# STM32103C8T6.net
KiCad netlist of a schematic drawn in Altium Designer
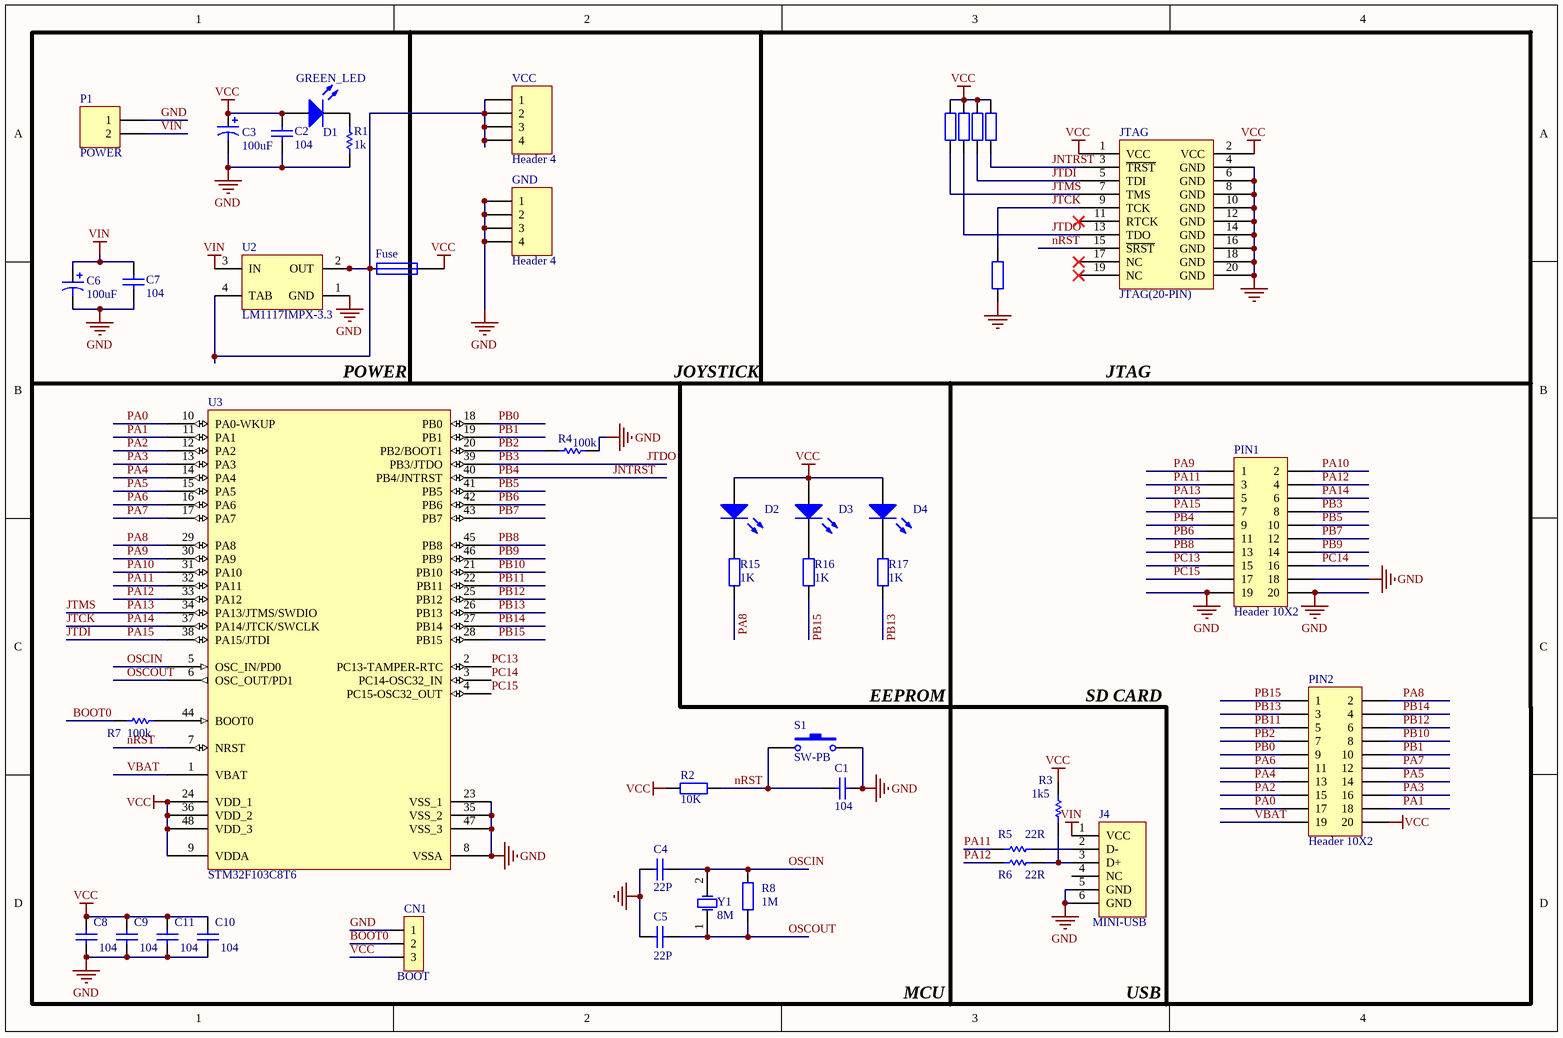
[diagram p0: STM32103C8T6.SchDoc]

(export (version "E")
  (design (tool "Eeschema 10.0.6"))
  (components
    (comp (ref "C1")
      (value "104")
      (footprint "0805")
      (description "Capacitor (Semiconductor SIM Model)")
      (fields (field (name "Comment") "Cap Semi") (field (name "PUBLISHER") "Altium Limited"))
      (libsource (lib "Miscellaneous Devices") (part "Cap Semi"))
    )
    (comp (ref "C2")
      (value "104")
      (footprint "0805")
      (description "Capacitor (Semiconductor SIM Model)")
      (fields (field (name "Comment") "Cap Semi") (field (name "PUBLISHER") "Altium Limited"))
      (libsource (lib "Miscellaneous Devices") (part "Cap Semi"))
    )
    (comp (ref "C3")
      (value "100uF")
      (footprint "1206")
      (description "Polarized Capacitor (Radial)")
      (fields (field (name "Comment") "Cap Pol1") (field (name "PUBLISHER") "Altium Limited"))
      (libsource (lib "Miscellaneous Devices") (part "Cap Pol1"))
    )
    (comp (ref "C4")
      (value "22P")
      (footprint "0805")
      (description "Capacitor")
      (fields (field (name "PUBLISHER") "Altium Limited"))
      (libsource (lib "Miscellaneous Devices") (part "Cap"))
    )
    (comp (ref "C5")
      (value "22P")
      (footprint "0805")
      (description "Capacitor")
      (fields (field (name "PUBLISHER") "Altium Limited"))
      (libsource (lib "Miscellaneous Devices") (part "Cap"))
    )
    (comp (ref "C6")
      (value "100uF")
      (footprint "1206")
      (description "Polarized Capacitor (Radial)")
      (fields (field (name "Comment") "Cap Pol1") (field (name "PUBLISHER") "Altium Limited"))
      (libsource (lib "Miscellaneous Devices") (part "Cap Pol1"))
    )
    (comp (ref "C7")
      (value "104")
      (footprint "0805")
      (description "Capacitor (Semiconductor SIM Model)")
      (fields (field (name "Comment") "Cap Semi") (field (name "PUBLISHER") "Altium Limited"))
      (libsource (lib "Miscellaneous Devices") (part "Cap Semi"))
    )
    (comp (ref "C8")
      (value "104")
      (footprint "0603")
      (description "Capacitor (Semiconductor SIM Model)")
      (fields (field (name "Comment") "Cap Semi") (field (name "PUBLISHER") "Altium Limited"))
      (libsource (lib "Miscellaneous Devices") (part "Cap Semi"))
    )
    (comp (ref "C9")
      (value "104")
      (footprint "0603")
      (description "Capacitor (Semiconductor SIM Model)")
      (fields (field (name "Comment") "Cap Semi") (field (name "PUBLISHER") "Altium Limited"))
      (libsource (lib "Miscellaneous Devices") (part "Cap Semi"))
    )
    (comp (ref "C10")
      (value "104")
      (footprint "0603")
      (description "Capacitor (Semiconductor SIM Model)")
      (fields (field (name "Comment") "Cap Semi") (field (name "PUBLISHER") "Altium Limited"))
      (libsource (lib "Miscellaneous Devices") (part "Cap Semi"))
    )
    (comp (ref "C11")
      (value "104")
      (footprint "0603")
      (description "Capacitor (Semiconductor SIM Model)")
      (fields (field (name "Comment") "Cap Semi") (field (name "PUBLISHER") "Altium Limited"))
      (libsource (lib "Miscellaneous Devices") (part "Cap Semi"))
    )
    (comp (ref "CN1") (value "BOOT") (footprint "KEY_22D00") (libsource (lib "Universal") (part "CON3")))
    (comp (ref "D1")
      (value "GREEN_LED")
      (footprint "LED_0805")
      (description "Typical BLUE SiC LED")
      (fields (field (name "PUBLISHER") "Altium Limited"))
      (libsource (lib "Miscellaneous Devices") (part "LED3"))
    )
    (comp (ref "D2")
      (value "LED0")
      (footprint "0805")
      (description "Typical INFRARED GaAs LED")
      (fields (field (name "PUBLISHER") "Altium Limited"))
      (libsource (lib "Miscellaneous Devices") (part "LED0"))
    )
    (comp (ref "D3")
      (value "LED0")
      (footprint "0805")
      (description "Typical INFRARED GaAs LED")
      (fields (field (name "PUBLISHER") "Altium Limited"))
      (libsource (lib "Miscellaneous Devices") (part "LED0"))
    )
    (comp (ref "D4")
      (value "LED0")
      (footprint "0805")
      (description "Typical INFRARED GaAs LED")
      (fields (field (name "PUBLISHER") "Altium Limited"))
      (libsource (lib "Miscellaneous Devices") (part "LED0"))
    )
    (comp (ref "Fuse")
      (value "Fuse 1")
      (footprint "0805")
      (description "Fuse")
      (fields (field (name "PUBLISHER") "Altium Limited"))
      (libsource (lib "Miscellaneous Devices") (part "Fuse 1"))
    )
    (comp (ref "GND")
      (value "Header 4")
      (footprint "HDR1X4")
      (description "Header, 4-Pin")
      (fields (field (name "PUBLISHER") "Altium Limited"))
      (libsource (lib "Miscellaneous Connectors") (part "Header 4"))
    )
    (comp (ref "J4")
      (value "MINI-USB")
      (footprint "MINI_USB")
      (libsource (lib "Universal") (part "USB-MINI"))
    )
    (comp (ref "JTAG")
      (value "JTAG(20-PIN)")
      (footprint "JP20_DOMNLOAD")
      (libsource (lib "LM3S_JTAG") (part "JTAG(20-PIN)"))
    )
    (comp (ref "P1")
      (value "POWER")
      (footprint "XH2.54-2")
      (description "Header, 2-Pin")
      (fields (field (name "PUBLISHER") "Altium Limited"))
      (libsource (lib "Miscellaneous Connectors") (part "Header 2"))
    )
    (comp (ref "PIN1")
      (value "Header 10X2")
      (footprint "HDR2X10")
      (description "Header, 10-Pin, Dual row")
      (fields (field (name "PUBLISHER") "Altium Limited"))
      (libsource (lib "Miscellaneous Connectors") (part "Header 10X2"))
    )
    (comp (ref "PIN2")
      (value "Header 10X2")
      (footprint "HDR2X10")
      (description "Header, 10-Pin, Dual row")
      (fields (field (name "PUBLISHER") "Altium Limited"))
      (libsource (lib "Miscellaneous Connectors") (part "Header 10X2"))
    )
    (comp (ref "R1")
      (value "1k")
      (footprint "0805")
      (description "Semiconductor Resistor")
      (fields (field (name "Comment") "Res Semi") (field (name "PUBLISHER") "Altium Limited"))
      (libsource (lib "Miscellaneous Devices") (part "Res Semi"))
    )
    (comp (ref "R2")
      (value "10K")
      (footprint "0805")
      (description "Resistor")
      (fields (field (name "Comment") "Res2") (field (name "PUBLISHER") "Altium Limited"))
      (libsource (lib "") (part "Res2_2"))
    )
    (comp (ref "R3")
      (value "1k5")
      (footprint "0805")
      (description "Semiconductor Resistor")
      (fields (field (name "Comment") "Res Semi") (field (name "PUBLISHER") "Altium Limited"))
      (libsource (lib "Miscellaneous Devices") (part "Res Semi"))
    )
    (comp (ref "R4")
      (value "100k")
      (footprint "0805")
      (description "Semiconductor Resistor")
      (fields (field (name "Comment") "Res Semi") (field (name "PUBLISHER") "Altium Limited"))
      (libsource (lib "Miscellaneous Devices") (part "Res Semi"))
    )
    (comp (ref "R5")
      (value "22R")
      (footprint "0805")
      (description "Semiconductor Resistor")
      (fields (field (name "Comment") "Res Semi") (field (name "PUBLISHER") "Altium Limited"))
      (libsource (lib "Miscellaneous Devices") (part "Res Semi"))
    )
    (comp (ref "R6")
      (value "22R")
      (footprint "0805")
      (description "Semiconductor Resistor")
      (fields (field (name "Comment") "Res Semi") (field (name "PUBLISHER") "Altium Limited"))
      (libsource (lib "Miscellaneous Devices") (part "Res Semi"))
    )
    (comp (ref "R7")
      (value "100k")
      (footprint "0805")
      (description "Semiconductor Resistor")
      (fields (field (name "Comment") "Res Semi") (field (name "PUBLISHER") "Altium Limited"))
      (libsource (lib "Miscellaneous Devices") (part "Res Semi"))
    )
    (comp (ref "R8")
      (value "1M")
      (footprint "0805")
      (description "Resistor")
      (fields (field (name "PUBLISHER") "Altium Limited"))
      (libsource (lib "") (part "Res2_1"))
    )
    (comp (ref "R10")
      (value "10K")
      (footprint "0805")
      (description "Resistor")
      (fields (field (name "PUBLISHER") "Altium Limited"))
      (libsource (lib "Miscellaneous Devices") (part "Res2"))
    )
    (comp (ref "R11")
      (value "10K")
      (footprint "0805")
      (description "Resistor")
      (fields (field (name "PUBLISHER") "Altium Limited"))
      (libsource (lib "Miscellaneous Devices") (part "Res2"))
    )
    (comp (ref "R12")
      (value "10K")
      (footprint "0805")
      (description "Resistor")
      (fields (field (name "PUBLISHER") "Altium Limited"))
      (libsource (lib "Miscellaneous Devices") (part "Res2"))
    )
    (comp (ref "R13")
      (value "10K")
      (footprint "0805")
      (description "Resistor")
      (fields (field (name "PUBLISHER") "Altium Limited"))
      (libsource (lib "Miscellaneous Devices") (part "Res2"))
    )
    (comp (ref "R14")
      (value "10K")
      (footprint "0805")
      (description "Resistor")
      (fields (field (name "PUBLISHER") "Altium Limited"))
      (libsource (lib "Miscellaneous Devices") (part "Res2"))
    )
    (comp (ref "R15")
      (value "1K")
      (footprint "0805")
      (description "Resistor")
      (fields (field (name "PUBLISHER") "Altium Limited"))
      (libsource (lib "") (part "Res2_1"))
    )
    (comp (ref "R16")
      (value "1K")
      (footprint "0805")
      (description "Resistor")
      (fields (field (name "PUBLISHER") "Altium Limited"))
      (libsource (lib "") (part "Res2_1"))
    )
    (comp (ref "R17")
      (value "1K")
      (footprint "0805")
      (description "Resistor")
      (fields (field (name "PUBLISHER") "Altium Limited"))
      (libsource (lib "") (part "Res2_1"))
    )
    (comp (ref "S1")
      (value "SW-PB")
      (footprint "棕色小按键开关")
      (description "Switch")
      (fields (field (name "PUBLISHER") "Altium Limited"))
      (libsource (lib "Miscellaneous Devices") (part "SW-PB"))
    )
    (comp (ref "U2")
      (value "LM1117IMPX-3.3")
      (footprint "MP04A_N")
      (description "800mA Low-Dropout Linear Regulator, 4-pin SOT-223")
      (fields
        (field (name "MANUFACTURER") "National Semiconductor")
        (field (name "PUBLISHER") "Altium Limited")
      )
      (libsource (lib "NSC LDO") (part "LM1117IMPX-3.3"))
    )
    (comp (ref "U3")
      (value "STM32F103C8T6")
      (footprint "LQFP48_L")
      (description "STM32 ARM-based 32-bit MCU with 64 Kbytes Flash, 48-pin LQFP, Industrial Temperature")
      (libsource (lib "ST Microcontroller 32-Bit STM32 SCH") (part "STM32F103C8T6"))
    )
    (comp (ref "VCC")
      (value "Header 4")
      (footprint "HDR1X4")
      (description "Header, 4-Pin")
      (fields (field (name "PUBLISHER") "Altium Limited"))
      (libsource (lib "Miscellaneous Connectors") (part "Header 4"))
    )
    (comp (ref "Y1")
      (value "8M")
      (footprint "XTAL")
      (description "Crystal Oscillator")
      (fields (field (name "PUBLISHER") "Altium Limited"))
      (libsource (lib "Miscellaneous Devices") (part "XTAL"))
    )
  )
  (nets
    (net (code "1") (name "/BOOT0") (class "Default")
      (node (ref "CN1") (pin "2") (pinfunction "2_2") (pintype "passive"))
      (node (ref "R7") (pin "1") (pinfunction "1_1") (pintype "passive"))
    )
    (net (code "2") (name "/JNTRST") (class "Default")
      (node (ref "JTAG") (pin "3") (pinfunction "~{TRST}_3") (pintype "passive"))
      (node (ref "PIN1") (pin "9") (pinfunction "9_9") (pintype "passive"))
      (node (ref "R14") (pin "1") (pinfunction "1_1") (pintype "passive"))
      (node (ref "U3") (pin "40") (pinfunction "PB4/JNTRST_40") (pintype "bidirectional"))
    )
    (net (code "3") (name "/JTCK") (class "Default")
      (node (ref "JTAG") (pin "9") (pinfunction "TCK_9") (pintype "passive"))
      (node (ref "PIN1") (pin "6") (pinfunction "6_6") (pintype "passive"))
      (node (ref "R10") (pin "2") (pinfunction "2_2") (pintype "passive"))
      (node (ref "U3") (pin "37") (pinfunction "PA14/JTCK/SWCLK_37") (pintype "bidirectional"))
    )
    (net (code "4") (name "/JTDI") (class "Default")
      (node (ref "JTAG") (pin "5") (pinfunction "TDI_5") (pintype "passive"))
      (node (ref "PIN1") (pin "7") (pinfunction "7_7") (pintype "passive"))
      (node (ref "R13") (pin "1") (pinfunction "1_1") (pintype "passive"))
      (node (ref "U3") (pin "38") (pinfunction "PA15/JTDI_38") (pintype "bidirectional"))
    )
    (net (code "5") (name "/JTDO") (class "Default")
      (node (ref "JTAG") (pin "13") (pinfunction "TDO_13") (pintype "passive"))
      (node (ref "PIN1") (pin "8") (pinfunction "8_8") (pintype "passive"))
      (node (ref "R12") (pin "1") (pinfunction "1_1") (pintype "passive"))
      (node (ref "U3") (pin "39") (pinfunction "PB3/JTDO_39") (pintype "bidirectional"))
    )
    (net (code "6") (name "/JTMS") (class "Default")
      (node (ref "JTAG") (pin "7") (pinfunction "TMS_7") (pintype "passive"))
      (node (ref "PIN1") (pin "5") (pinfunction "5_5") (pintype "passive"))
      (node (ref "R11") (pin "1") (pinfunction "1_1") (pintype "passive"))
      (node (ref "U3") (pin "34") (pinfunction "PA13/JTMS/SWDIO_34") (pintype "bidirectional"))
    )
    (net (code "7") (name "/OSCIN") (class "Default")
      (node (ref "C4") (pin "1") (pinfunction "1_1") (pintype "passive"))
      (node (ref "R8") (pin "2") (pinfunction "2_2") (pintype "passive"))
      (node (ref "U3") (pin "5") (pinfunction "OSC_IN/PD0_5") (pintype "input"))
      (node (ref "Y1") (pin "2") (pinfunction "OSC2_2") (pintype "passive"))
    )
    (net (code "8") (name "/OSCOUT") (class "Default")
      (node (ref "C5") (pin "1") (pinfunction "1_1") (pintype "passive"))
      (node (ref "R8") (pin "1") (pinfunction "1_1") (pintype "passive"))
      (node (ref "U3") (pin "6") (pinfunction "OSC_OUT/PD1_6") (pintype "output"))
      (node (ref "Y1") (pin "1") (pinfunction "OSC1_1") (pintype "passive"))
    )
    (net (code "9") (name "/PA0") (class "Default")
      (node (ref "PIN2") (pin "17") (pinfunction "17_17") (pintype "passive"))
      (node (ref "U3") (pin "10") (pinfunction "PA0-WKUP_10") (pintype "bidirectional"))
    )
    (net (code "10") (name "/PA1") (class "Default")
      (node (ref "PIN2") (pin "18") (pinfunction "18_18") (pintype "passive"))
      (node (ref "U3") (pin "11") (pinfunction "PA1_11") (pintype "bidirectional"))
    )
    (net (code "11") (name "/PA2") (class "Default")
      (node (ref "PIN2") (pin "15") (pinfunction "15_15") (pintype "passive"))
      (node (ref "U3") (pin "12") (pinfunction "PA2_12") (pintype "bidirectional"))
    )
    (net (code "12") (name "/PA3") (class "Default")
      (node (ref "PIN2") (pin "16") (pinfunction "16_16") (pintype "passive"))
      (node (ref "U3") (pin "13") (pinfunction "PA3_13") (pintype "bidirectional"))
    )
    (net (code "13") (name "/PA4") (class "Default")
      (node (ref "PIN2") (pin "13") (pinfunction "13_13") (pintype "passive"))
      (node (ref "U3") (pin "14") (pinfunction "PA4_14") (pintype "bidirectional"))
    )
    (net (code "14") (name "/PA5") (class "Default")
      (node (ref "PIN2") (pin "14") (pinfunction "14_14") (pintype "passive"))
      (node (ref "U3") (pin "15") (pinfunction "PA5_15") (pintype "bidirectional"))
    )
    (net (code "15") (name "/PA6") (class "Default")
      (node (ref "PIN2") (pin "11") (pinfunction "11_11") (pintype "passive"))
      (node (ref "U3") (pin "16") (pinfunction "PA6_16") (pintype "bidirectional"))
    )
    (net (code "16") (name "/PA7") (class "Default")
      (node (ref "PIN2") (pin "12") (pinfunction "12_12") (pintype "passive"))
      (node (ref "U3") (pin "17") (pinfunction "PA7_17") (pintype "bidirectional"))
    )
    (net (code "17") (name "/PA8") (class "Default")
      (node (ref "PIN2") (pin "2") (pinfunction "2_2") (pintype "passive"))
      (node (ref "R15") (pin "1") (pinfunction "1_1") (pintype "passive"))
      (node (ref "U3") (pin "29") (pinfunction "PA8_29") (pintype "bidirectional"))
    )
    (net (code "18") (name "/PA9") (class "Default")
      (node (ref "PIN1") (pin "1") (pinfunction "1_1") (pintype "passive"))
      (node (ref "U3") (pin "30") (pinfunction "PA9_30") (pintype "bidirectional"))
    )
    (net (code "19") (name "/PA10") (class "Default")
      (node (ref "PIN1") (pin "2") (pinfunction "2_2") (pintype "passive"))
      (node (ref "U3") (pin "31") (pinfunction "PA10_31") (pintype "bidirectional"))
    )
    (net (code "20") (name "/PA11") (class "Default")
      (node (ref "PIN1") (pin "3") (pinfunction "3_3") (pintype "passive"))
      (node (ref "R5") (pin "1") (pinfunction "1_1") (pintype "passive"))
      (node (ref "U3") (pin "32") (pinfunction "PA11_32") (pintype "bidirectional"))
    )
    (net (code "21") (name "/PA12") (class "Default")
      (node (ref "PIN1") (pin "4") (pinfunction "4_4") (pintype "passive"))
      (node (ref "R6") (pin "1") (pinfunction "1_1") (pintype "passive"))
      (node (ref "U3") (pin "33") (pinfunction "PA12_33") (pintype "bidirectional"))
    )
    (net (code "22") (name "/PB0") (class "Default")
      (node (ref "PIN2") (pin "9") (pinfunction "9_9") (pintype "passive"))
      (node (ref "U3") (pin "18") (pinfunction "PB0_18") (pintype "bidirectional"))
    )
    (net (code "23") (name "/PB1") (class "Default")
      (node (ref "PIN2") (pin "10") (pinfunction "10_10") (pintype "passive"))
      (node (ref "U3") (pin "19") (pinfunction "PB1_19") (pintype "bidirectional"))
    )
    (net (code "24") (name "/PB2") (class "Default")
      (node (ref "PIN2") (pin "7") (pinfunction "7_7") (pintype "passive"))
      (node (ref "R4") (pin "1") (pinfunction "1_1") (pintype "passive"))
      (node (ref "U3") (pin "20") (pinfunction "PB2/BOOT1_20") (pintype "bidirectional"))
    )
    (net (code "25") (name "/PB5") (class "Default")
      (node (ref "PIN1") (pin "10") (pinfunction "10_10") (pintype "passive"))
      (node (ref "U3") (pin "41") (pinfunction "PB5_41") (pintype "bidirectional"))
    )
    (net (code "26") (name "/PB6") (class "Default")
      (node (ref "PIN1") (pin "11") (pinfunction "11_11") (pintype "passive"))
      (node (ref "U3") (pin "42") (pinfunction "PB6_42") (pintype "bidirectional"))
    )
    (net (code "27") (name "/PB7") (class "Default")
      (node (ref "PIN1") (pin "12") (pinfunction "12_12") (pintype "passive"))
      (node (ref "U3") (pin "43") (pinfunction "PB7_43") (pintype "bidirectional"))
    )
    (net (code "28") (name "/PB8") (class "Default")
      (node (ref "PIN1") (pin "13") (pinfunction "13_13") (pintype "passive"))
      (node (ref "U3") (pin "45") (pinfunction "PB8_45") (pintype "bidirectional"))
    )
    (net (code "29") (name "/PB9") (class "Default")
      (node (ref "PIN1") (pin "14") (pinfunction "14_14") (pintype "passive"))
      (node (ref "U3") (pin "46") (pinfunction "PB9_46") (pintype "bidirectional"))
    )
    (net (code "30") (name "/PB10") (class "Default")
      (node (ref "PIN2") (pin "8") (pinfunction "8_8") (pintype "passive"))
      (node (ref "U3") (pin "21") (pinfunction "PB10_21") (pintype "bidirectional"))
    )
    (net (code "31") (name "/PB11") (class "Default")
      (node (ref "PIN2") (pin "5") (pinfunction "5_5") (pintype "passive"))
      (node (ref "U3") (pin "22") (pinfunction "PB11_22") (pintype "bidirectional"))
    )
    (net (code "32") (name "/PB12") (class "Default")
      (node (ref "PIN2") (pin "6") (pinfunction "6_6") (pintype "passive"))
      (node (ref "U3") (pin "25") (pinfunction "PB12_25") (pintype "bidirectional"))
    )
    (net (code "33") (name "/PB13") (class "Default")
      (node (ref "PIN2") (pin "3") (pinfunction "3_3") (pintype "passive"))
      (node (ref "R17") (pin "1") (pinfunction "1_1") (pintype "passive"))
      (node (ref "U3") (pin "26") (pinfunction "PB13_26") (pintype "bidirectional"))
    )
    (net (code "34") (name "/PB14") (class "Default")
      (node (ref "PIN2") (pin "4") (pinfunction "4_4") (pintype "passive"))
      (node (ref "U3") (pin "27") (pinfunction "PB14_27") (pintype "bidirectional"))
    )
    (net (code "35") (name "/PB15") (class "Default")
      (node (ref "PIN2") (pin "1") (pinfunction "1_1") (pintype "passive"))
      (node (ref "R16") (pin "1") (pinfunction "1_1") (pintype "passive"))
      (node (ref "U3") (pin "28") (pinfunction "PB15_28") (pintype "bidirectional"))
    )
    (net (code "36") (name "/PC13") (class "Default")
      (node (ref "PIN1") (pin "15") (pinfunction "15_15") (pintype "passive"))
      (node (ref "U3") (pin "2") (pinfunction "PC13-TAMPER-RTC_2") (pintype "bidirectional"))
    )
    (net (code "37") (name "/PC14") (class "Default")
      (node (ref "PIN1") (pin "16") (pinfunction "16_16") (pintype "passive"))
      (node (ref "U3") (pin "3") (pinfunction "PC14-OSC32_IN_3") (pintype "bidirectional"))
    )
    (net (code "38") (name "/PC15") (class "Default")
      (node (ref "PIN1") (pin "17") (pinfunction "17_17") (pintype "passive"))
      (node (ref "U3") (pin "4") (pinfunction "PC15-OSC32_OUT_4") (pintype "bidirectional"))
    )
    (net (code "39") (name "/VBAT") (class "Default")
      (node (ref "PIN2") (pin "19") (pinfunction "19_19") (pintype "passive"))
      (node (ref "U3") (pin "1") (pinfunction "VBAT_1") (pintype "power_in"))
    )
    (net (code "40") (name "/nRST") (class "Default")
      (node (ref "C1") (pin "1") (pinfunction "1_1") (pintype "passive"))
      (node (ref "JTAG") (pin "15") (pinfunction "~{SRST}_15") (pintype "passive"))
      (node (ref "R2") (pin "2") (pinfunction "2_2") (pintype "passive"))
      (node (ref "S1") (pin "1") (pinfunction "1_1") (pintype "passive"))
      (node (ref "U3") (pin "7") (pinfunction "NRST_7") (pintype "bidirectional"))
    )
    (net (code "41") (name "GND") (class "Default")
      (node (ref "C1") (pin "2") (pinfunction "2_2") (pintype "passive"))
      (node (ref "C10") (pin "2") (pinfunction "2_2") (pintype "passive"))
      (node (ref "C11") (pin "2") (pinfunction "2_2") (pintype "passive"))
      (node (ref "C2") (pin "2") (pinfunction "2_2") (pintype "passive"))
      (node (ref "C3") (pin "2") (pinfunction "2_2") (pintype "passive"))
      (node (ref "C4") (pin "2") (pinfunction "2_2") (pintype "passive"))
      (node (ref "C5") (pin "2") (pinfunction "2_2") (pintype "passive"))
      (node (ref "C6") (pin "2") (pinfunction "2_2") (pintype "passive"))
      (node (ref "C7") (pin "2") (pinfunction "2_2") (pintype "passive"))
      (node (ref "C8") (pin "2") (pinfunction "2_2") (pintype "passive"))
      (node (ref "C9") (pin "2") (pinfunction "2_2") (pintype "passive"))
      (node (ref "CN1") (pin "1") (pinfunction "1_1") (pintype "passive"))
      (node (ref "GND") (pin "1") (pinfunction "1_1") (pintype "passive"))
      (node (ref "GND") (pin "2") (pinfunction "2_2") (pintype "passive"))
      (node (ref "GND") (pin "3") (pinfunction "3_3") (pintype "passive"))
      (node (ref "GND") (pin "4") (pinfunction "4_4") (pintype "passive"))
      (node (ref "J4") (pin "5") (pinfunction "GND_5") (pintype "passive"))
      (node (ref "J4") (pin "6") (pinfunction "GND_6") (pintype "passive"))
      (node (ref "JTAG") (pin "10") (pinfunction "GND_10") (pintype "passive"))
      (node (ref "JTAG") (pin "12") (pinfunction "GND_12") (pintype "passive"))
      (node (ref "JTAG") (pin "14") (pinfunction "GND_14") (pintype "passive"))
      (node (ref "JTAG") (pin "16") (pinfunction "GND_16") (pintype "passive"))
      (node (ref "JTAG") (pin "18") (pinfunction "GND_18") (pintype "passive"))
      (node (ref "JTAG") (pin "20") (pinfunction "GND_20") (pintype "passive"))
      (node (ref "JTAG") (pin "4") (pinfunction "GND_4") (pintype "passive"))
      (node (ref "JTAG") (pin "6") (pinfunction "GND_6") (pintype "passive"))
      (node (ref "JTAG") (pin "8") (pinfunction "GND_8") (pintype "passive"))
      (node (ref "P1") (pin "1") (pinfunction "1_1") (pintype "passive"))
      (node (ref "PIN1") (pin "18") (pinfunction "18_18") (pintype "passive"))
      (node (ref "PIN1") (pin "19") (pinfunction "19_19") (pintype "passive"))
      (node (ref "PIN1") (pin "20") (pinfunction "20_20") (pintype "passive"))
      (node (ref "R1") (pin "1") (pinfunction "1_1") (pintype "passive"))
      (node (ref "R10") (pin "1") (pinfunction "1_1") (pintype "passive"))
      (node (ref "R4") (pin "2") (pinfunction "2_2") (pintype "passive"))
      (node (ref "S1") (pin "2") (pinfunction "2_2") (pintype "passive"))
      (node (ref "U2") (pin "1") (pinfunction "GND_1") (pintype "power_in"))
      (node (ref "U3") (pin "23") (pinfunction "VSS_1_23") (pintype "power_in"))
      (node (ref "U3") (pin "35") (pinfunction "VSS_2_35") (pintype "power_in"))
      (node (ref "U3") (pin "47") (pinfunction "VSS_3_47") (pintype "power_in"))
      (node (ref "U3") (pin "8") (pinfunction "VSSA_8") (pintype "power_in"))
    )
    (net (code "42") (name "Net-(D1-K)") (class "Default")
      (node (ref "D1") (pin "2") (pinfunction "K_2") (pintype "passive"))
      (node (ref "R1") (pin "2") (pinfunction "2_2") (pintype "passive"))
    )
    (net (code "43") (name "Net-(D2-K)") (class "Default")
      (node (ref "D2") (pin "2") (pinfunction "K_2") (pintype "passive"))
      (node (ref "R15") (pin "2") (pinfunction "2_2") (pintype "passive"))
    )
    (net (code "44") (name "Net-(D3-K)") (class "Default")
      (node (ref "D3") (pin "2") (pinfunction "K_2") (pintype "passive"))
      (node (ref "R16") (pin "2") (pinfunction "2_2") (pintype "passive"))
    )
    (net (code "45") (name "Net-(D4-K)") (class "Default")
      (node (ref "D4") (pin "2") (pinfunction "K_2") (pintype "passive"))
      (node (ref "R17") (pin "2") (pinfunction "2_2") (pintype "passive"))
    )
    (net (code "46") (name "Net-(J4-D+)") (class "Default")
      (node (ref "J4") (pin "3") (pinfunction "D+_3") (pintype "passive"))
      (node (ref "R3") (pin "1") (pinfunction "1_1") (pintype "passive"))
      (node (ref "R6") (pin "2") (pinfunction "2_2") (pintype "passive"))
    )
    (net (code "47") (name "Net-(J4-D-)") (class "Default")
      (node (ref "J4") (pin "2") (pinfunction "D-_2") (pintype "passive"))
      (node (ref "R5") (pin "2") (pinfunction "2_2") (pintype "passive"))
    )
    (net (code "48") (name "Net-(U2-OUT)") (class "Default")
      (node (ref "Fuse") (pin "2") (pinfunction "2_2") (pintype "passive"))
      (node (ref "U2") (pin "2") (pinfunction "OUT_2") (pintype "power_in"))
      (node (ref "U2") (pin "4") (pinfunction "TAB_4") (pintype "power_in"))
      (node (ref "VCC") (pin "1") (pinfunction "1_1") (pintype "passive"))
      (node (ref "VCC") (pin "2") (pinfunction "2_2") (pintype "passive"))
      (node (ref "VCC") (pin "3") (pinfunction "3_3") (pintype "passive"))
      (node (ref "VCC") (pin "4") (pinfunction "4_4") (pintype "passive"))
    )
    (net (code "49") (name "Net-(U3-BOOT0)") (class "Default")
      (node (ref "R7") (pin "2") (pinfunction "2_2") (pintype "passive"))
      (node (ref "U3") (pin "44") (pinfunction "BOOT0_44") (pintype "input"))
    )
    (net (code "50") (name "VCC") (class "Default")
      (node (ref "C10") (pin "1") (pinfunction "1_1") (pintype "passive"))
      (node (ref "C11") (pin "1") (pinfunction "1_1") (pintype "passive"))
      (node (ref "C2") (pin "1") (pinfunction "1_1") (pintype "passive"))
      (node (ref "C3") (pin "1") (pinfunction "1_1") (pintype "passive"))
      (node (ref "C8") (pin "1") (pinfunction "1_1") (pintype "passive"))
      (node (ref "C9") (pin "1") (pinfunction "1_1") (pintype "passive"))
      (node (ref "CN1") (pin "3") (pinfunction "3_3") (pintype "passive"))
      (node (ref "D1") (pin "1") (pinfunction "A_1") (pintype "passive"))
      (node (ref "D2") (pin "1") (pinfunction "A_1") (pintype "passive"))
      (node (ref "D3") (pin "1") (pinfunction "A_1") (pintype "passive"))
      (node (ref "D4") (pin "1") (pinfunction "A_1") (pintype "passive"))
      (node (ref "Fuse") (pin "1") (pinfunction "1_1") (pintype "passive"))
      (node (ref "JTAG") (pin "1") (pinfunction "VCC_1") (pintype "passive"))
      (node (ref "JTAG") (pin "2") (pinfunction "VCC_2") (pintype "passive"))
      (node (ref "PIN2") (pin "20") (pinfunction "20_20") (pintype "passive"))
      (node (ref "R11") (pin "2") (pinfunction "2_2") (pintype "passive"))
      (node (ref "R12") (pin "2") (pinfunction "2_2") (pintype "passive"))
      (node (ref "R13") (pin "2") (pinfunction "2_2") (pintype "passive"))
      (node (ref "R14") (pin "2") (pinfunction "2_2") (pintype "passive"))
      (node (ref "R2") (pin "1") (pinfunction "1_1") (pintype "passive"))
      (node (ref "R3") (pin "2") (pinfunction "2_2") (pintype "passive"))
      (node (ref "U3") (pin "24") (pinfunction "VDD_1_24") (pintype "power_in"))
      (node (ref "U3") (pin "36") (pinfunction "VDD_2_36") (pintype "power_in"))
      (node (ref "U3") (pin "48") (pinfunction "VDD_3_48") (pintype "power_in"))
      (node (ref "U3") (pin "9") (pinfunction "VDDA_9") (pintype "power_in"))
    )
    (net (code "51") (name "VIN") (class "Default")
      (node (ref "C6") (pin "1") (pinfunction "1_1") (pintype "passive"))
      (node (ref "C7") (pin "1") (pinfunction "1_1") (pintype "passive"))
      (node (ref "J4") (pin "1") (pinfunction "VCC_1") (pintype "passive"))
      (node (ref "P1") (pin "2") (pinfunction "2_2") (pintype "passive"))
      (node (ref "U2") (pin "3") (pinfunction "IN_3") (pintype "power_in"))
    )
    (net (code "52") (name "unconnected-(J4-NC-Pad4)") (class "Default")
      (node (ref "J4") (pin "4") (pinfunction "NC_4") (pintype "passive"))
    )
    (net (code "53") (name "unconnected-(JTAG-NC-Pad17)") (class "Default")
      (node (ref "JTAG") (pin "17") (pinfunction "NC_17") (pintype "passive+no_connect"))
    )
    (net (code "54") (name "unconnected-(JTAG-NC-Pad19)") (class "Default")
      (node (ref "JTAG") (pin "19") (pinfunction "NC_19") (pintype "passive+no_connect"))
    )
    (net (code "55") (name "unconnected-(JTAG-RTCK-Pad11)") (class "Default")
      (node (ref "JTAG") (pin "11") (pinfunction "RTCK_11") (pintype "passive+no_connect"))
    )
  )
)
